# MM-08_FPS-400.net
KiCad netlist of a schematic drawn in Altium Designer
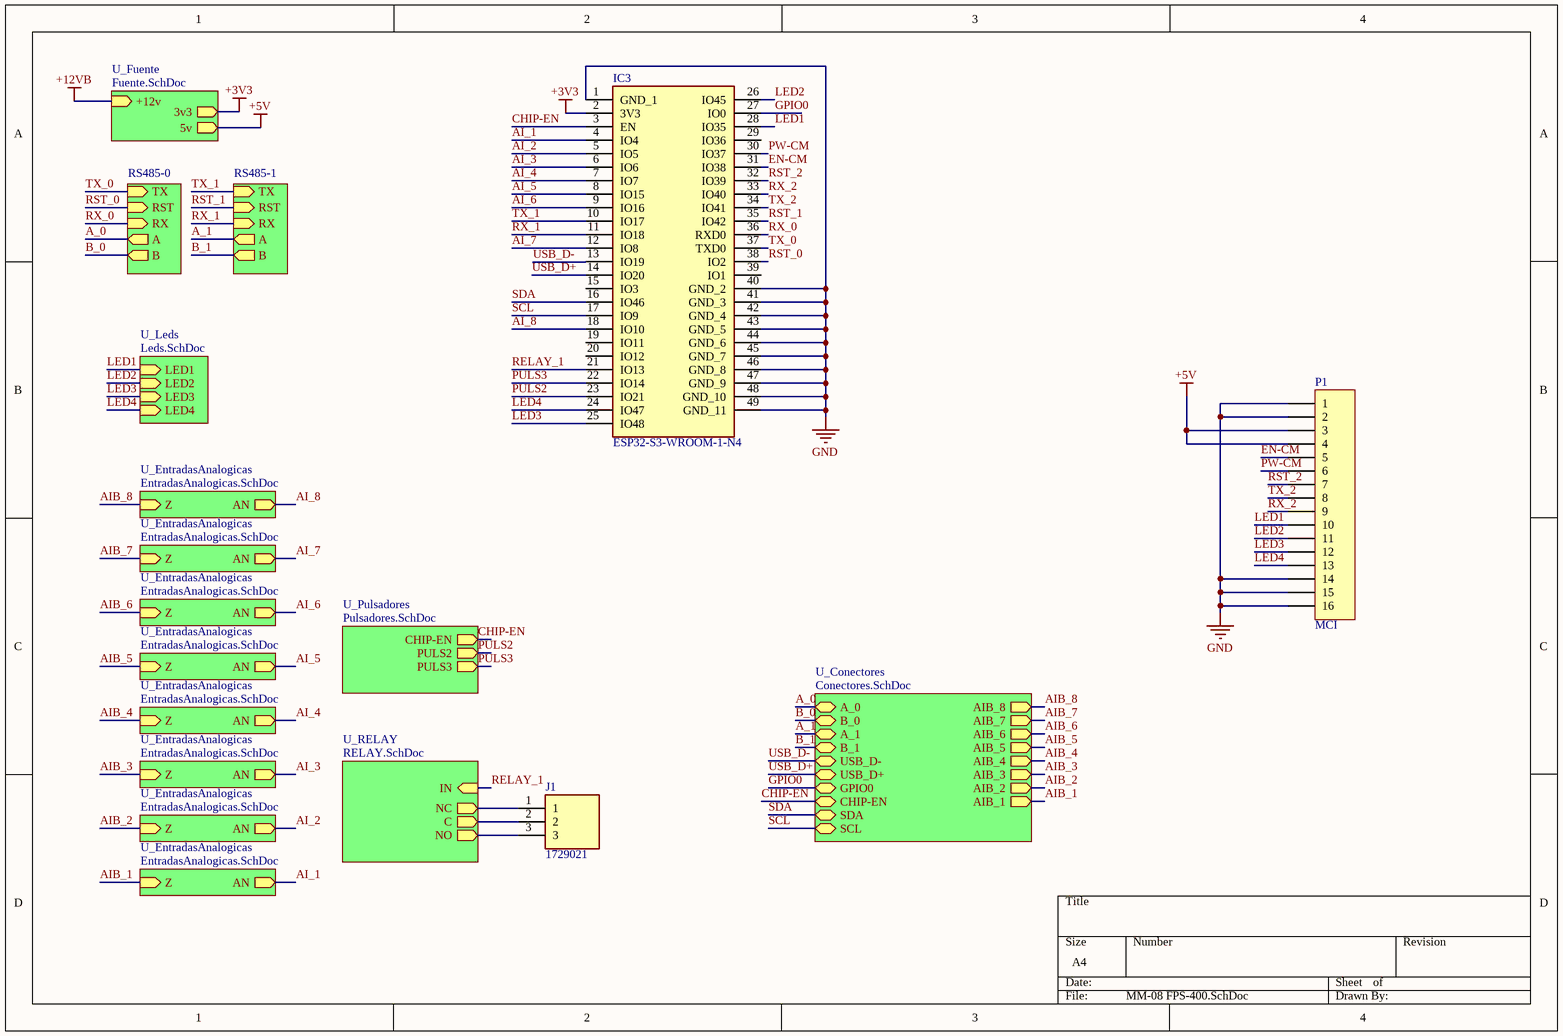
[diagram p0: MM-08 FPS-400.SchDoc]

(export (version "E")
  (design (tool "Eeschema 10.0.6"))
  (components
    (comp (ref "IC3")
      (value "ESP32-S3-WROOM-1-N4")
      (footprint "SamacSys:Model Name")
      (description "Integrated Circuit")
      (fields (field (name "MOUSER PART NUMBER") "356-ESP32-S3WROOM1N4"))
      (libsource (lib "CPU FPS-400 2022") (part "ESP32-S3-WROOM-1-N4"))
    )
    (comp (ref "J1")
      (value "1729021")
      (footprint "SamacSys:1729021")
      (description "Connector")
      (fields (field (name "MOUSER PART NUMBER") "651-1729021"))
      (libsource (lib "*") (part "1729021"))
    )
    (comp (ref "P1")
      (value "MCI")
      (footprint "HDR1X16")
      (description "Header, 16-Pin")
      (fields (field (name "PUBLISHER") "Altium Limited"))
      (libsource (lib "Miscellaneous Connectors") (part "Header 16"))
    )
  )
  (nets
    (net (code "1") (name "+3V3") (class "Default")
      (node (ref "IC3") (pin "2") (pinfunction "3V3_2") (pintype "passive"))
    )
    (net (code "2") (name "+5V") (class "Default")
      (node (ref "P1") (pin "3") (pinfunction "3_3") (pintype "passive"))
      (node (ref "P1") (pin "4") (pinfunction "4_4") (pintype "passive"))
    )
    (net (code "12") (name "/AI_1") (class "Default")
      (node (ref "IC3") (pin "4") (pinfunction "IO4_4") (pintype "passive"))
    )
    (net (code "13") (name "/AI_2") (class "Default")
      (node (ref "IC3") (pin "5") (pinfunction "IO5_5") (pintype "passive"))
    )
    (net (code "14") (name "/AI_3") (class "Default")
      (node (ref "IC3") (pin "6") (pinfunction "IO6_6") (pintype "passive"))
    )
    (net (code "15") (name "/AI_4") (class "Default")
      (node (ref "IC3") (pin "7") (pinfunction "IO7_7") (pintype "passive"))
    )
    (net (code "16") (name "/AI_5") (class "Default")
      (node (ref "IC3") (pin "8") (pinfunction "IO15_8") (pintype "passive"))
    )
    (net (code "17") (name "/AI_6") (class "Default")
      (node (ref "IC3") (pin "9") (pinfunction "IO16_9") (pintype "passive"))
    )
    (net (code "18") (name "/AI_7") (class "Default")
      (node (ref "IC3") (pin "12") (pinfunction "IO8_12") (pintype "passive"))
    )
    (net (code "19") (name "/AI_8") (class "Default")
      (node (ref "IC3") (pin "18") (pinfunction "IO10_18") (pintype "passive"))
    )
    (net (code "24") (name "/C") (class "Default")
      (node (ref "J1") (pin "2") (pinfunction "2_2") (pintype "passive"))
    )
    (net (code "25") (name "/CHIP-EN") (class "Default")
      (node (ref "IC3") (pin "3") (pinfunction "EN_3") (pintype "passive"))
    )
    (net (code "26") (name "/EN-CM") (class "Default")
      (node (ref "IC3") (pin "31") (pinfunction "IO38_31") (pintype "passive"))
      (node (ref "P1") (pin "5") (pinfunction "5_5") (pintype "passive"))
    )
    (net (code "27") (name "/GPIO0") (class "Default")
      (node (ref "IC3") (pin "27") (pinfunction "IO0_27") (pintype "passive"))
    )
    (net (code "28") (name "/LED1") (class "Default")
      (node (ref "IC3") (pin "28") (pinfunction "IO35_28") (pintype "passive"))
      (node (ref "P1") (pin "10") (pinfunction "10_10") (pintype "passive"))
    )
    (net (code "29") (name "/LED2") (class "Default")
      (node (ref "IC3") (pin "26") (pinfunction "IO45_26") (pintype "passive"))
      (node (ref "P1") (pin "11") (pinfunction "11_11") (pintype "passive"))
    )
    (net (code "30") (name "/LED3") (class "Default")
      (node (ref "IC3") (pin "25") (pinfunction "IO48_25") (pintype "passive"))
      (node (ref "P1") (pin "12") (pinfunction "12_12") (pintype "passive"))
    )
    (net (code "31") (name "/LED4") (class "Default")
      (node (ref "IC3") (pin "24") (pinfunction "IO47_24") (pintype "passive"))
      (node (ref "P1") (pin "13") (pinfunction "13_13") (pintype "passive"))
    )
    (net (code "32") (name "/NC") (class "Default")
      (node (ref "J1") (pin "1") (pinfunction "1_1") (pintype "passive"))
    )
    (net (code "33") (name "/NO") (class "Default")
      (node (ref "J1") (pin "3") (pinfunction "3_3") (pintype "passive"))
    )
    (net (code "34") (name "/PULS2") (class "Default")
      (node (ref "IC3") (pin "23") (pinfunction "IO21_23") (pintype "passive"))
    )
    (net (code "35") (name "/PULS3") (class "Default")
      (node (ref "IC3") (pin "22") (pinfunction "IO14_22") (pintype "passive"))
    )
    (net (code "36") (name "/PW-CM") (class "Default")
      (node (ref "IC3") (pin "30") (pinfunction "IO37_30") (pintype "passive"))
      (node (ref "P1") (pin "6") (pinfunction "6_6") (pintype "passive"))
    )
    (net (code "37") (name "/RELAY_1") (class "Default")
      (node (ref "IC3") (pin "21") (pinfunction "IO13_21") (pintype "passive"))
    )
    (net (code "38") (name "/RST_0") (class "Default")
      (node (ref "IC3") (pin "38") (pinfunction "IO2_38") (pintype "passive"))
    )
    (net (code "39") (name "/RST_1") (class "Default")
      (node (ref "IC3") (pin "35") (pinfunction "IO42_35") (pintype "passive"))
    )
    (net (code "40") (name "/RST_2") (class "Default")
      (node (ref "IC3") (pin "32") (pinfunction "IO39_32") (pintype "passive"))
      (node (ref "P1") (pin "7") (pinfunction "7_7") (pintype "passive"))
    )
    (net (code "41") (name "/RX_0") (class "Default")
      (node (ref "IC3") (pin "36") (pinfunction "RXD0_36") (pintype "passive"))
    )
    (net (code "42") (name "/RX_1") (class "Default")
      (node (ref "IC3") (pin "11") (pinfunction "IO18_11") (pintype "passive"))
    )
    (net (code "43") (name "/RX_2") (class "Default")
      (node (ref "IC3") (pin "33") (pinfunction "IO40_33") (pintype "passive"))
      (node (ref "P1") (pin "9") (pinfunction "9_9") (pintype "passive"))
    )
    (net (code "44") (name "/SCL") (class "Default")
      (node (ref "IC3") (pin "17") (pinfunction "IO9_17") (pintype "passive"))
    )
    (net (code "45") (name "/SDA") (class "Default")
      (node (ref "IC3") (pin "16") (pinfunction "IO46_16") (pintype "passive"))
    )
    (net (code "46") (name "/TX_0") (class "Default")
      (node (ref "IC3") (pin "37") (pinfunction "TXD0_37") (pintype "passive"))
    )
    (net (code "47") (name "/TX_1") (class "Default")
      (node (ref "IC3") (pin "10") (pinfunction "IO17_10") (pintype "passive"))
    )
    (net (code "48") (name "/TX_2") (class "Default")
      (node (ref "IC3") (pin "34") (pinfunction "IO41_34") (pintype "passive"))
      (node (ref "P1") (pin "8") (pinfunction "8_8") (pintype "passive"))
    )
    (net (code "49") (name "/USB_D+") (class "Default")
      (node (ref "IC3") (pin "14") (pinfunction "IO20_14") (pintype "passive"))
    )
    (net (code "50") (name "/USB_D-") (class "Default")
      (node (ref "IC3") (pin "13") (pinfunction "IO19_13") (pintype "passive"))
    )
    (net (code "51") (name "GND") (class "Default")
      (node (ref "IC3") (pin "1") (pinfunction "GND_1_1") (pintype "passive"))
      (node (ref "IC3") (pin "40") (pinfunction "GND_2_40") (pintype "passive"))
      (node (ref "IC3") (pin "41") (pinfunction "GND_3_41") (pintype "passive"))
      (node (ref "IC3") (pin "42") (pinfunction "GND_4_42") (pintype "passive"))
      (node (ref "IC3") (pin "43") (pinfunction "GND_5_43") (pintype "passive"))
      (node (ref "IC3") (pin "44") (pinfunction "GND_6_44") (pintype "passive"))
      (node (ref "IC3") (pin "45") (pinfunction "GND_7_45") (pintype "passive"))
      (node (ref "IC3") (pin "46") (pinfunction "GND_8_46") (pintype "passive"))
      (node (ref "IC3") (pin "47") (pinfunction "GND_9_47") (pintype "passive"))
      (node (ref "IC3") (pin "48") (pinfunction "GND_10_48") (pintype "passive"))
      (node (ref "IC3") (pin "49") (pinfunction "GND_11_49") (pintype "passive"))
      (node (ref "P1") (pin "1") (pinfunction "1_1") (pintype "passive"))
      (node (ref "P1") (pin "14") (pinfunction "14_14") (pintype "passive"))
      (node (ref "P1") (pin "15") (pinfunction "15_15") (pintype "passive"))
      (node (ref "P1") (pin "16") (pinfunction "16_16") (pintype "passive"))
      (node (ref "P1") (pin "2") (pinfunction "2_2") (pintype "passive"))
    )
    (net (code "52") (name "unconnected-(IC3-IO1-Pad39)") (class "Default")
      (node (ref "IC3") (pin "39") (pinfunction "IO1_39") (pintype "passive"))
    )
    (net (code "53") (name "unconnected-(IC3-IO3-Pad15)") (class "Default")
      (node (ref "IC3") (pin "15") (pinfunction "IO3_15") (pintype "passive"))
    )
    (net (code "54") (name "unconnected-(IC3-IO11-Pad19)") (class "Default")
      (node (ref "IC3") (pin "19") (pinfunction "IO11_19") (pintype "passive"))
    )
    (net (code "55") (name "unconnected-(IC3-IO12-Pad20)") (class "Default")
      (node (ref "IC3") (pin "20") (pinfunction "IO12_20") (pintype "passive"))
    )
    (net (code "56") (name "unconnected-(IC3-IO36-Pad29)") (class "Default")
      (node (ref "IC3") (pin "29") (pinfunction "IO36_29") (pintype "passive"))
    )
  )
)
